# Test.net
KiCad netlist of a schematic drawn in Altium Designer
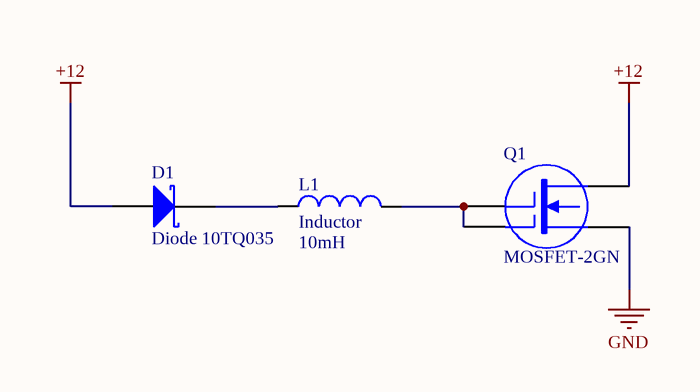
[diagram p0: Test.SchDoc]

(export (version "E")
  (design (tool "Eeschema 10.0.6"))
  (components
    (comp (ref "D1")
      (value "Diode 10TQ035")
      (footprint "TO-220AC")
      (description "Schottky Rectifier")
      (fields (field (name "PUBLISHER") "Altium Limited"))
      (libsource (lib "Miscellaneous Devices") (part "Diode 10TQ035"))
    )
    (comp (ref "L1")
      (value "Inductor")
      (footprint "0402-A")
      (fields (field (name "ALTIUM_VALUE") "10mH") (field (name "PUBLISHER") "Altium Limited"))
      (libsource (lib "Miscellaneous Devices") (part "Inductor"))
    )
    (comp (ref "Q1")
      (value "MOSFET-2GN")
      (footprint "T05A")
      (description "Two-Gate, N-Channel MOSFET")
      (fields (field (name "PUBLISHER") "Altium Limited"))
      (libsource (lib "Miscellaneous Devices") (part "MOSFET-2GN"))
    )
  )
  (nets
    (net (code "1") (name "+12") (class "Default")
      (node (ref "D1") (pin "3") (pinfunction "A_3") (pintype "passive"))
      (node (ref "Q1") (pin "3") (pinfunction "D_3") (pintype "passive"))
    )
    (net (code "2") (name "GND") (class "Default")
      (node (ref "Q1") (pin "4") (pinfunction "S_4") (pintype "passive"))
    )
    (net (code "3") (name "Net-(D1-K)") (class "Default")
      (node (ref "D1") (pin "1") (pinfunction "K_1") (pintype "passive"))
      (node (ref "L1") (pin "1") (pinfunction "1_1") (pintype "passive"))
    )
    (net (code "4") (name "Net-(Q1-G1)") (class "Default")
      (node (ref "L1") (pin "2") (pinfunction "2_2") (pintype "passive"))
      (node (ref "Q1") (pin "1") (pinfunction "G1_1") (pintype "passive"))
      (node (ref "Q1") (pin "2") (pinfunction "G2_2") (pintype "passive"))
    )
  )
)
